# marquee-neopixel.net
KiCad netlist of a schematic drawn in EAGLE
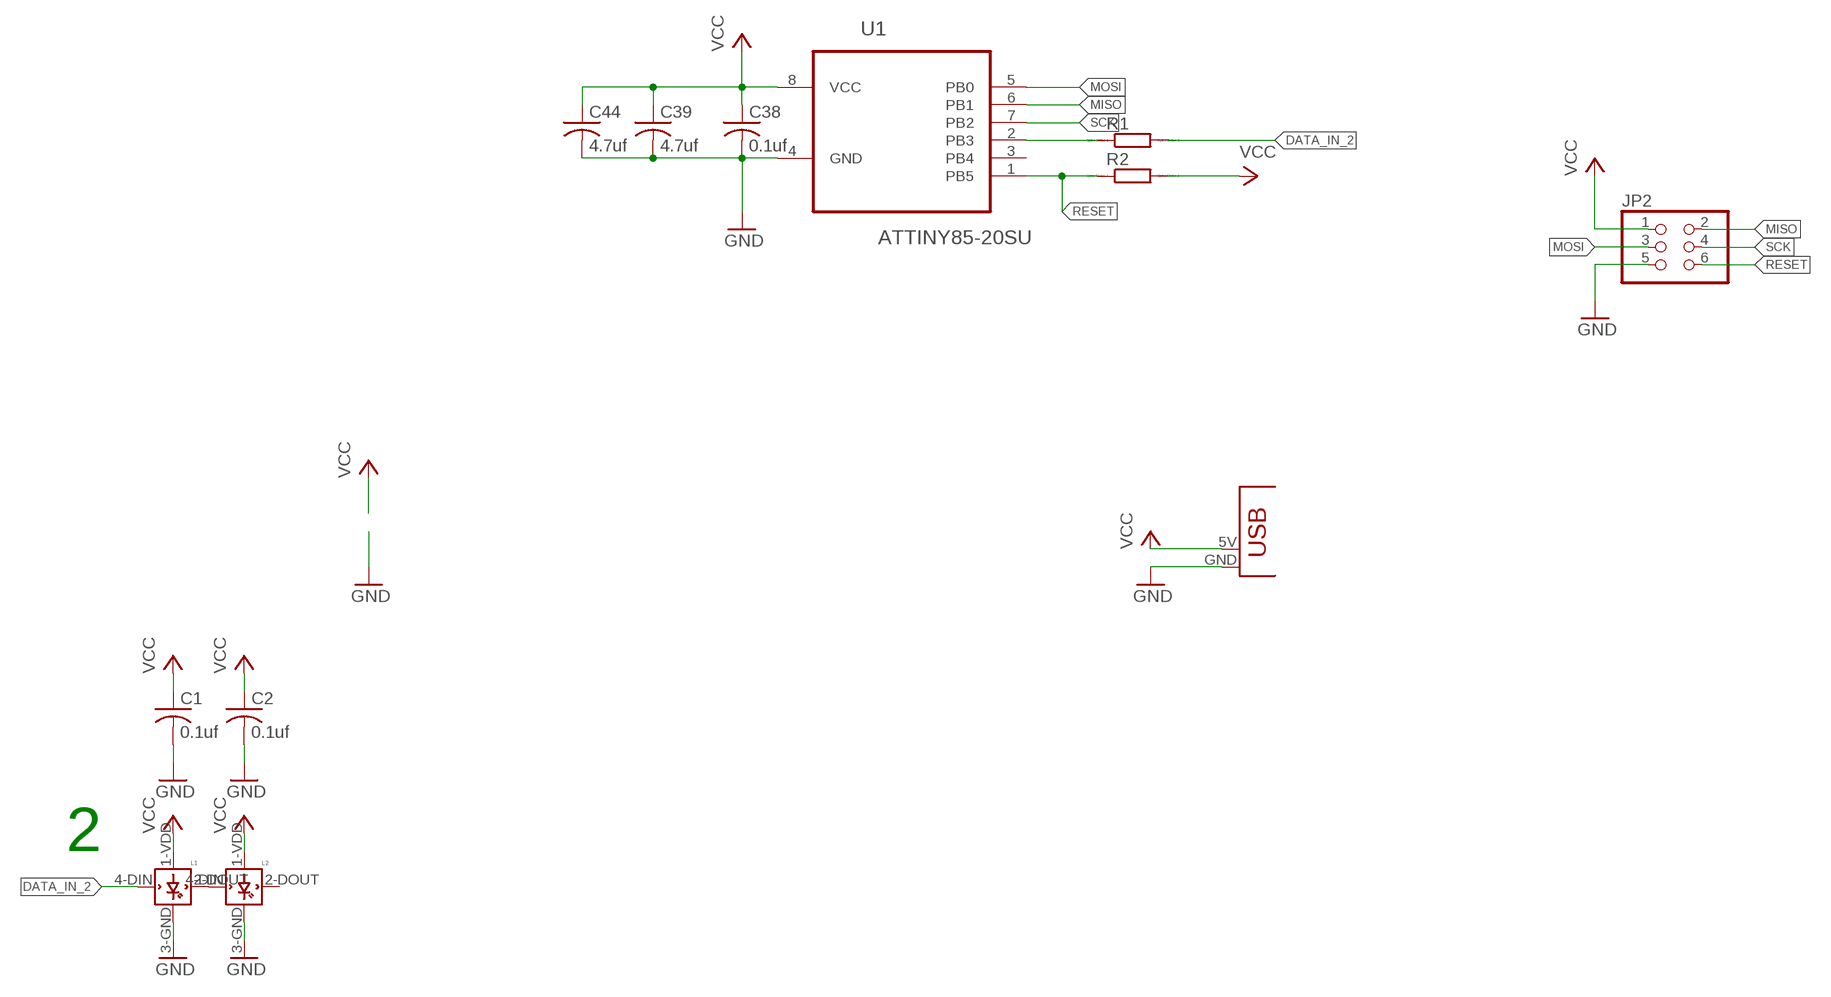
[diagram p0: schematic, sheet 1]

(export (version "E")
  (design (tool "Eeschema 10.0.6"))
  (components
    (comp (ref "C1")
      (value "0.1uf")
      (footprint "eagle-import:C0603")
      (libsource (lib "eagle-import") (part "C-USC0603"))
    )
    (comp (ref "C2")
      (value "0.1uf")
      (footprint "eagle-import:C0603")
      (libsource (lib "eagle-import") (part "C-USC0603"))
    )
    (comp (ref "C38")
      (value "0.1uf")
      (footprint "eagle-import:C0603")
      (libsource (lib "eagle-import") (part "C-USC0603"))
    )
    (comp (ref "C39")
      (value "4.7uf")
      (footprint "eagle-import:C0603")
      (libsource (lib "eagle-import") (part "C-USC0603"))
    )
    (comp (ref "C44")
      (value "4.7uf")
      (footprint "eagle-import:C0603")
      (libsource (lib "eagle-import") (part "C-USC0603"))
    )
    (comp (ref "JP2")
      (value "PINHD-2X3")
      (footprint "eagle-import:2X03")
      (libsource (lib "eagle-import") (part "PINHD-2X3"))
    )
    (comp (ref "L1")
      (value "WS2812B")
      (footprint "eagle-import:WS2812B")
      (fields (field (name "SPICEPREFIX") "E"))
      (libsource (lib "eagle-import") (part "WS2812B"))
    )
    (comp (ref "L2")
      (value "WS2812B")
      (footprint "eagle-import:WS2812B")
      (fields (field (name "SPICEPREFIX") "E"))
      (libsource (lib "eagle-import") (part "WS2812B"))
    )
    (comp (ref "R1")
      (value "RR0603")
      (footprint "eagle-import:R0603")
      (libsource (lib "eagle-import") (part "RR0603"))
    )
    (comp (ref "R2")
      (value "RR0603")
      (footprint "eagle-import:R0603")
      (libsource (lib "eagle-import") (part "RR0603"))
    )
    (comp (ref "U$1")
      (value "USB-POWER-ONLY")
      (footprint "eagle-import:USB-A-PCB-POWER-ONLY")
      (libsource (lib "eagle-import") (part "USB-POWER-ONLY"))
    )
    (comp (ref "U1")
      (value "ATTINY85-20SU")
      (footprint "eagle-import:SOIC127P798X216-8N")
      (libsource (lib "eagle-import") (part "ATTINY85-20SU"))
    )
  )
  (nets
    (net (code "1") (name "DATA_IN_2") (class "Default")
      (node (ref "L1") (pin "4-DIN") (pinfunction "DIN_4-DIN") (pintype "input"))
      (node (ref "R1") (pin "2") (pinfunction "2_2") (pintype "passive"))
    )
    (net (code "2") (name "GND") (class "Default")
      (node (ref "C1") (pin "2") (pinfunction "2_2") (pintype "passive"))
      (node (ref "C2") (pin "2") (pinfunction "2_2") (pintype "passive"))
      (node (ref "C38") (pin "2") (pinfunction "2_2") (pintype "passive"))
      (node (ref "C39") (pin "2") (pinfunction "2_2") (pintype "passive"))
      (node (ref "C44") (pin "2") (pinfunction "2_2") (pintype "passive"))
      (node (ref "JP2") (pin "5") (pinfunction "5_5") (pintype "passive"))
      (node (ref "L1") (pin "3-GND") (pinfunction "GND_3-GND") (pintype "bidirectional"))
      (node (ref "L2") (pin "3-GND") (pinfunction "GND_3-GND") (pintype "bidirectional"))
      (node (ref "U$1") (pin "GND") (pinfunction "GND_GND") (pintype "bidirectional"))
      (node (ref "U1") (pin "4") (pinfunction "GND_4") (pintype "passive"))
    )
    (net (code "3") (name "MISO") (class "Default")
      (node (ref "JP2") (pin "2") (pinfunction "2_2") (pintype "passive"))
      (node (ref "U1") (pin "6") (pinfunction "PB1_6") (pintype "bidirectional"))
    )
    (net (code "4") (name "MOSI") (class "Default")
      (node (ref "JP2") (pin "3") (pinfunction "3_3") (pintype "passive"))
      (node (ref "U1") (pin "5") (pinfunction "PB0_5") (pintype "bidirectional"))
    )
    (net (code "5") (name "Net-(L1-DOUT)") (class "Default")
      (node (ref "L1") (pin "2-DOUT") (pinfunction "DOUT_2-DOUT") (pintype "output"))
      (node (ref "L2") (pin "4-DIN") (pinfunction "DIN_4-DIN") (pintype "input"))
    )
    (net (code "6") (name "Net-(U1-PB3)") (class "Default")
      (node (ref "R1") (pin "1") (pinfunction "1_1") (pintype "passive"))
      (node (ref "U1") (pin "2") (pinfunction "PB3_2") (pintype "bidirectional"))
    )
    (net (code "7") (name "RESET") (class "Default")
      (node (ref "JP2") (pin "6") (pinfunction "6_6") (pintype "passive"))
      (node (ref "R2") (pin "1") (pinfunction "1_1") (pintype "passive"))
      (node (ref "U1") (pin "1") (pinfunction "PB5_1") (pintype "bidirectional"))
    )
    (net (code "8") (name "SCK") (class "Default")
      (node (ref "JP2") (pin "4") (pinfunction "4_4") (pintype "passive"))
      (node (ref "U1") (pin "7") (pinfunction "PB2_7") (pintype "bidirectional"))
    )
    (net (code "9") (name "VCC") (class "Default")
      (node (ref "C1") (pin "1") (pinfunction "1_1") (pintype "passive"))
      (node (ref "C2") (pin "1") (pinfunction "1_1") (pintype "passive"))
      (node (ref "C38") (pin "1") (pinfunction "1_1") (pintype "passive"))
      (node (ref "C39") (pin "1") (pinfunction "1_1") (pintype "passive"))
      (node (ref "C44") (pin "1") (pinfunction "1_1") (pintype "passive"))
      (node (ref "JP2") (pin "1") (pinfunction "1_1") (pintype "passive"))
      (node (ref "L1") (pin "1-VDD") (pinfunction "VDD_1-VDD") (pintype "bidirectional"))
      (node (ref "L2") (pin "1-VDD") (pinfunction "VDD_1-VDD") (pintype "bidirectional"))
      (node (ref "R2") (pin "2") (pinfunction "2_2") (pintype "passive"))
      (node (ref "U$1") (pin "5V") (pinfunction "VBUS_5V") (pintype "bidirectional"))
      (node (ref "U1") (pin "8") (pinfunction "VCC_8") (pintype "power_in"))
    )
    (net (code "10") (name "unconnected-(L2-DOUT-Pad2-DOUT)") (class "Default")
      (node (ref "L2") (pin "2-DOUT") (pinfunction "DOUT_2-DOUT") (pintype "output"))
    )
    (net (code "11") (name "unconnected-(U1-PB4-Pad3)") (class "Default")
      (node (ref "U1") (pin "3") (pinfunction "PB4_3") (pintype "bidirectional"))
    )
  )
)
